# UI.net
KiCad netlist of a schematic drawn in Altium Designer
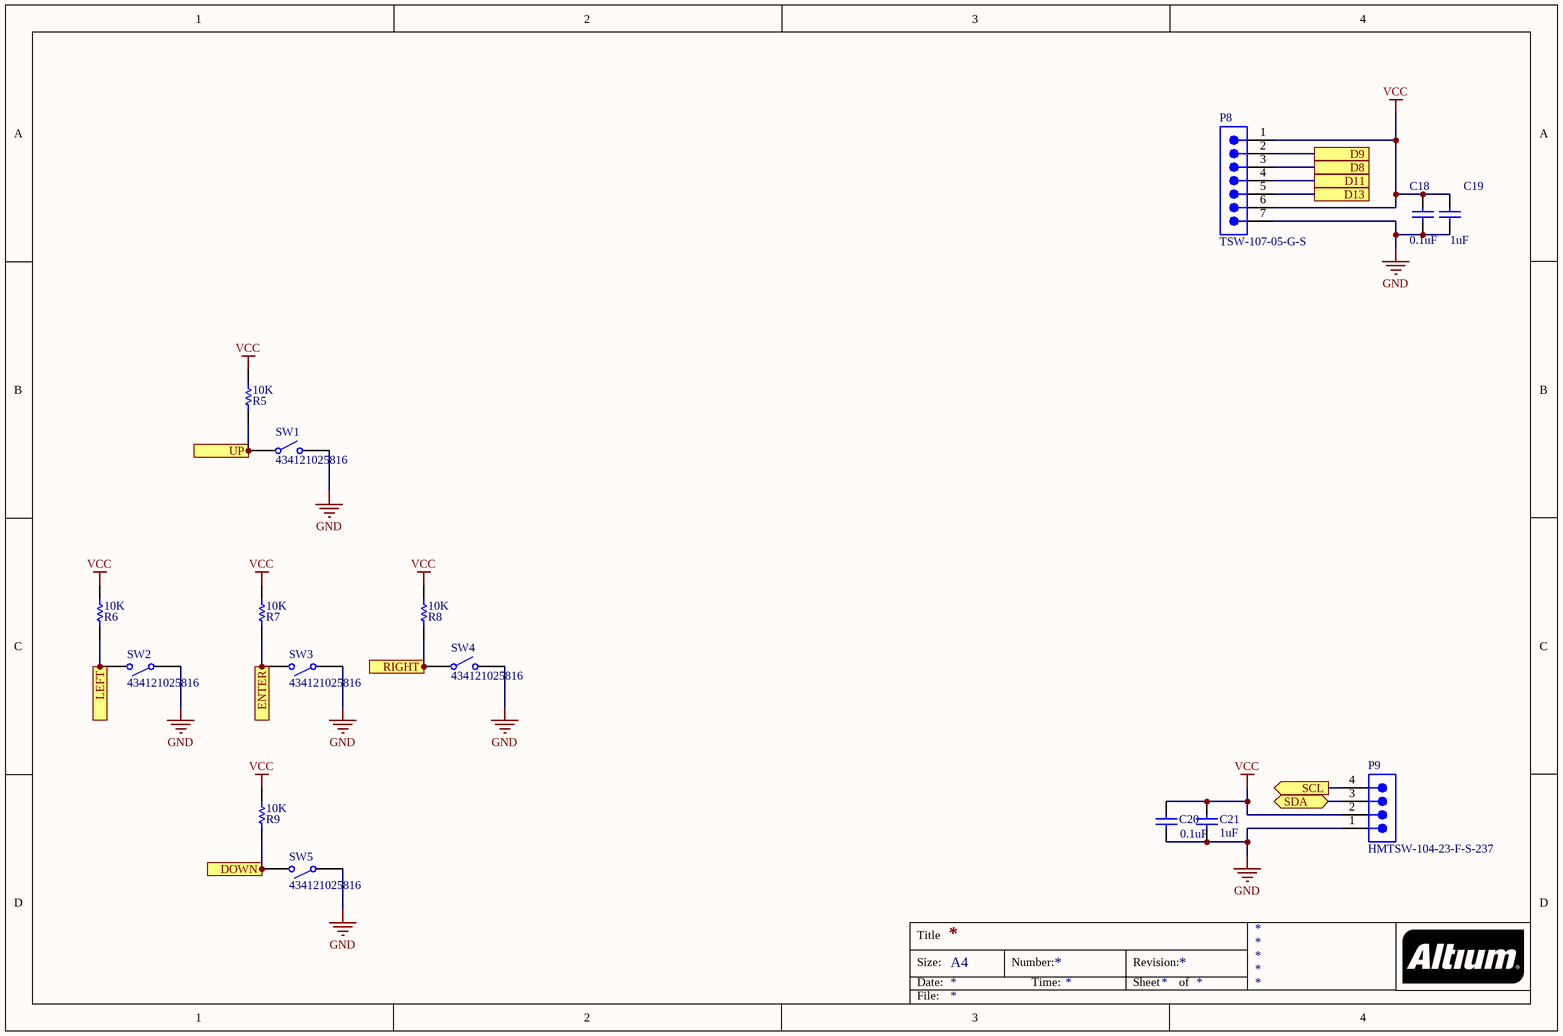
[diagram p0: UI.SchDoc]

(export (version "E")
  (design (tool "Eeschema 10.0.6"))
  (components
    (comp (ref "C18")
      (value "0.1uF")
      (footprint "CAPC0603(1608)100_M")
      (description "CAP 20pF 25V ±0.25pF 0603 (1608 Metric) Thickness 1mm SMD")
      (fields (field (name "TOLERANCE") "Â±0.25pF"))
      (libsource (lib "Altium Content Vault") (part "CAP"))
    )
    (comp (ref "C19")
      (value "1uF")
      (footprint "CAPC0603(1608)100_M")
      (description "CAP 20pF 25V ±0.25pF 0603 (1608 Metric) Thickness 1mm SMD")
      (fields (field (name "TOLERANCE") "Â±0.25pF"))
      (libsource (lib "Altium Content Vault") (part "CAP"))
    )
    (comp (ref "C20")
      (value "0.1uF")
      (footprint "CAPC0603(1608)100_M")
      (description "CAP 20pF 25V ±0.25pF 0603 (1608 Metric) Thickness 1mm SMD")
      (fields (field (name "TOLERANCE") "Â±0.25pF"))
      (libsource (lib "Altium Content Vault") (part "CAP"))
    )
    (comp (ref "C21")
      (value "1uF")
      (footprint "CAPC0603(1608)100_M")
      (description "CAP 20pF 25V ±0.25pF 0603 (1608 Metric) Thickness 1mm SMD")
      (fields (field (name "TOLERANCE") "Â±0.25pF"))
      (libsource (lib "Altium Content Vault") (part "CAP"))
    )
    (comp (ref "P8")
      (value "TSW-107-05-G-S")
      (footprint "SMTC-TSW-107-05-X-S")
      (description "0.025\" SQ Post Header, Through-hole, Vertical, -55 to 125 degC, 2.54 mm Pitch, 7-Pin, Male, RoHS")
      (fields (field (name "MANUFACTURER") "Samtec"))
      (libsource (lib "Altium Content Vault") (part "SMTC-TSW-107-05-X-S"))
    )
    (comp (ref "P9")
      (value "HMTSW-104-23-F-S-237")
      (footprint "SMTC-HMTSW-104-23-X-S-237")
      (fields (field (name "MANUFACTURER") "Samtec"))
      (libsource (lib "Altium Content Vault") (part "SMTC-HMTSW-104-23-X-S-237"))
    )
    (comp (ref "R5")
      (value "10K")
      (footprint "RESC1608X55X25ML10T15")
      (description "Chip Resistor, 4.7 KOhm, +/- 5%, 100 mW, -55 to 155 degC, 0603 (1608 Metric), RoHS, Tape and Reel")
      (fields (field (name "TOLERANCE") "5%") (field (name "MANUFACTURER") "Yageo"))
      (libsource (lib "Altium Content Vault") (part "RES-2"))
    )
    (comp (ref "R6")
      (value "10K")
      (footprint "RESC1608X55X25ML10T15")
      (description "Chip Resistor, 4.7 KOhm, +/- 5%, 100 mW, -55 to 155 degC, 0603 (1608 Metric), RoHS, Tape and Reel")
      (fields (field (name "TOLERANCE") "5%") (field (name "MANUFACTURER") "Yageo"))
      (libsource (lib "Altium Content Vault") (part "RES-2"))
    )
    (comp (ref "R7")
      (value "10K")
      (footprint "RESC1608X55X25ML10T15")
      (description "Chip Resistor, 4.7 KOhm, +/- 5%, 100 mW, -55 to 155 degC, 0603 (1608 Metric), RoHS, Tape and Reel")
      (fields (field (name "TOLERANCE") "5%") (field (name "MANUFACTURER") "Yageo"))
      (libsource (lib "Altium Content Vault") (part "RES-2"))
    )
    (comp (ref "R8")
      (value "10K")
      (footprint "RESC1608X55X25ML10T15")
      (description "Chip Resistor, 4.7 KOhm, +/- 5%, 100 mW, -55 to 155 degC, 0603 (1608 Metric), RoHS, Tape and Reel")
      (fields (field (name "TOLERANCE") "5%") (field (name "MANUFACTURER") "Yageo"))
      (libsource (lib "Altium Content Vault") (part "RES-2"))
    )
    (comp (ref "R9")
      (value "10K")
      (footprint "RESC1608X55X25ML10T15")
      (description "Chip Resistor, 4.7 KOhm, +/- 5%, 100 mW, -55 to 155 degC, 0603 (1608 Metric), RoHS, Tape and Reel")
      (fields (field (name "TOLERANCE") "5%") (field (name "MANUFACTURER") "Yageo"))
      (libsource (lib "Altium Content Vault") (part "RES-2"))
    )
    (comp (ref "SW1")
      (value "434121025816")
      (footprint "434121025816")
      (description "WS-TASV SMD Tact Switch 6.0X3.8 mm")
      (fields (field (name "MANUFACTURER") "Wuerth Elektronik"))
      (libsource (lib "Altium Content Vault") (part "WE-TACT-SW-2"))
    )
    (comp (ref "SW2")
      (value "434121025816")
      (footprint "434121025816")
      (description "WS-TASV SMD Tact Switch 6.0X3.8 mm")
      (fields (field (name "MANUFACTURER") "Wuerth Elektronik"))
      (libsource (lib "Altium Content Vault") (part "WE-TACT-SW-2"))
    )
    (comp (ref "SW3")
      (value "434121025816")
      (footprint "434121025816")
      (description "WS-TASV SMD Tact Switch 6.0X3.8 mm")
      (fields (field (name "MANUFACTURER") "Wuerth Elektronik"))
      (libsource (lib "Altium Content Vault") (part "WE-TACT-SW-2"))
    )
    (comp (ref "SW4")
      (value "434121025816")
      (footprint "434121025816")
      (description "WS-TASV SMD Tact Switch 6.0X3.8 mm")
      (fields (field (name "MANUFACTURER") "Wuerth Elektronik"))
      (libsource (lib "Altium Content Vault") (part "WE-TACT-SW-2"))
    )
    (comp (ref "SW5")
      (value "434121025816")
      (footprint "434121025816")
      (description "WS-TASV SMD Tact Switch 6.0X3.8 mm")
      (fields (field (name "MANUFACTURER") "Wuerth Elektronik"))
      (libsource (lib "Altium Content Vault") (part "WE-TACT-SW-2"))
    )
  )
  (nets
    (net (code "1") (name "/D8") (class "Default")
      (node (ref "P8") (pin "3") (pinfunction "3_3") (pintype "passive"))
    )
    (net (code "2") (name "/D9") (class "Default")
      (node (ref "P8") (pin "2") (pinfunction "2_2") (pintype "passive"))
    )
    (net (code "3") (name "/D11") (class "Default")
      (node (ref "P8") (pin "4") (pinfunction "4_4") (pintype "passive"))
    )
    (net (code "4") (name "/D13") (class "Default")
      (node (ref "P8") (pin "5") (pinfunction "5_5") (pintype "passive"))
    )
    (net (code "5") (name "/DOWN") (class "Default")
      (node (ref "R9") (pin "1") (pinfunction "1_1") (pintype "passive"))
      (node (ref "SW5") (pin "2") (pinfunction "2_2") (pintype "passive"))
    )
    (net (code "6") (name "/ENTER") (class "Default")
      (node (ref "R7") (pin "1") (pinfunction "1_1") (pintype "passive"))
      (node (ref "SW3") (pin "2") (pinfunction "2_2") (pintype "passive"))
    )
    (net (code "7") (name "/LEFT") (class "Default")
      (node (ref "R6") (pin "1") (pinfunction "1_1") (pintype "passive"))
      (node (ref "SW2") (pin "2") (pinfunction "2_2") (pintype "passive"))
    )
    (net (code "8") (name "/RIGHT") (class "Default")
      (node (ref "R8") (pin "1") (pinfunction "1_1") (pintype "passive"))
      (node (ref "SW4") (pin "1") (pinfunction "1_1") (pintype "passive"))
    )
    (net (code "9") (name "/SCL") (class "Default")
      (node (ref "P9") (pin "4") (pinfunction "4_4") (pintype "passive"))
    )
    (net (code "10") (name "/SDA") (class "Default")
      (node (ref "P9") (pin "3") (pinfunction "3_3") (pintype "passive"))
    )
    (net (code "11") (name "/UP") (class "Default")
      (node (ref "R5") (pin "1") (pinfunction "1_1") (pintype "passive"))
      (node (ref "SW1") (pin "1") (pinfunction "1_1") (pintype "passive"))
    )
    (net (code "12") (name "GND") (class "Default")
      (node (ref "C18") (pin "2") (pinfunction "2_2") (pintype "passive"))
      (node (ref "C19") (pin "2") (pinfunction "2_2") (pintype "passive"))
      (node (ref "C20") (pin "2") (pinfunction "2_2") (pintype "passive"))
      (node (ref "C21") (pin "2") (pinfunction "2_2") (pintype "passive"))
      (node (ref "P8") (pin "7") (pinfunction "7_7") (pintype "passive"))
      (node (ref "P9") (pin "1") (pinfunction "1_1") (pintype "passive"))
      (node (ref "SW1") (pin "2") (pinfunction "2_2") (pintype "passive"))
      (node (ref "SW2") (pin "1") (pinfunction "1_1") (pintype "passive"))
      (node (ref "SW3") (pin "1") (pinfunction "1_1") (pintype "passive"))
      (node (ref "SW4") (pin "2") (pinfunction "2_2") (pintype "passive"))
      (node (ref "SW5") (pin "1") (pinfunction "1_1") (pintype "passive"))
    )
    (net (code "13") (name "VCC") (class "Default")
      (node (ref "C18") (pin "1") (pinfunction "1_1") (pintype "passive"))
      (node (ref "C19") (pin "1") (pinfunction "1_1") (pintype "passive"))
      (node (ref "C20") (pin "1") (pinfunction "1_1") (pintype "passive"))
      (node (ref "C21") (pin "1") (pinfunction "1_1") (pintype "passive"))
      (node (ref "P8") (pin "1") (pinfunction "1_1") (pintype "passive"))
      (node (ref "P8") (pin "6") (pinfunction "6_6") (pintype "passive"))
      (node (ref "P9") (pin "2") (pinfunction "2_2") (pintype "passive"))
      (node (ref "R5") (pin "2") (pinfunction "2_2") (pintype "passive"))
      (node (ref "R6") (pin "2") (pinfunction "2_2") (pintype "passive"))
      (node (ref "R7") (pin "2") (pinfunction "2_2") (pintype "passive"))
      (node (ref "R8") (pin "2") (pinfunction "2_2") (pintype "passive"))
      (node (ref "R9") (pin "2") (pinfunction "2_2") (pintype "passive"))
    )
  )
)
